# PCB_sch_iter1.net
KiCad netlist of a schematic drawn in EAGLE
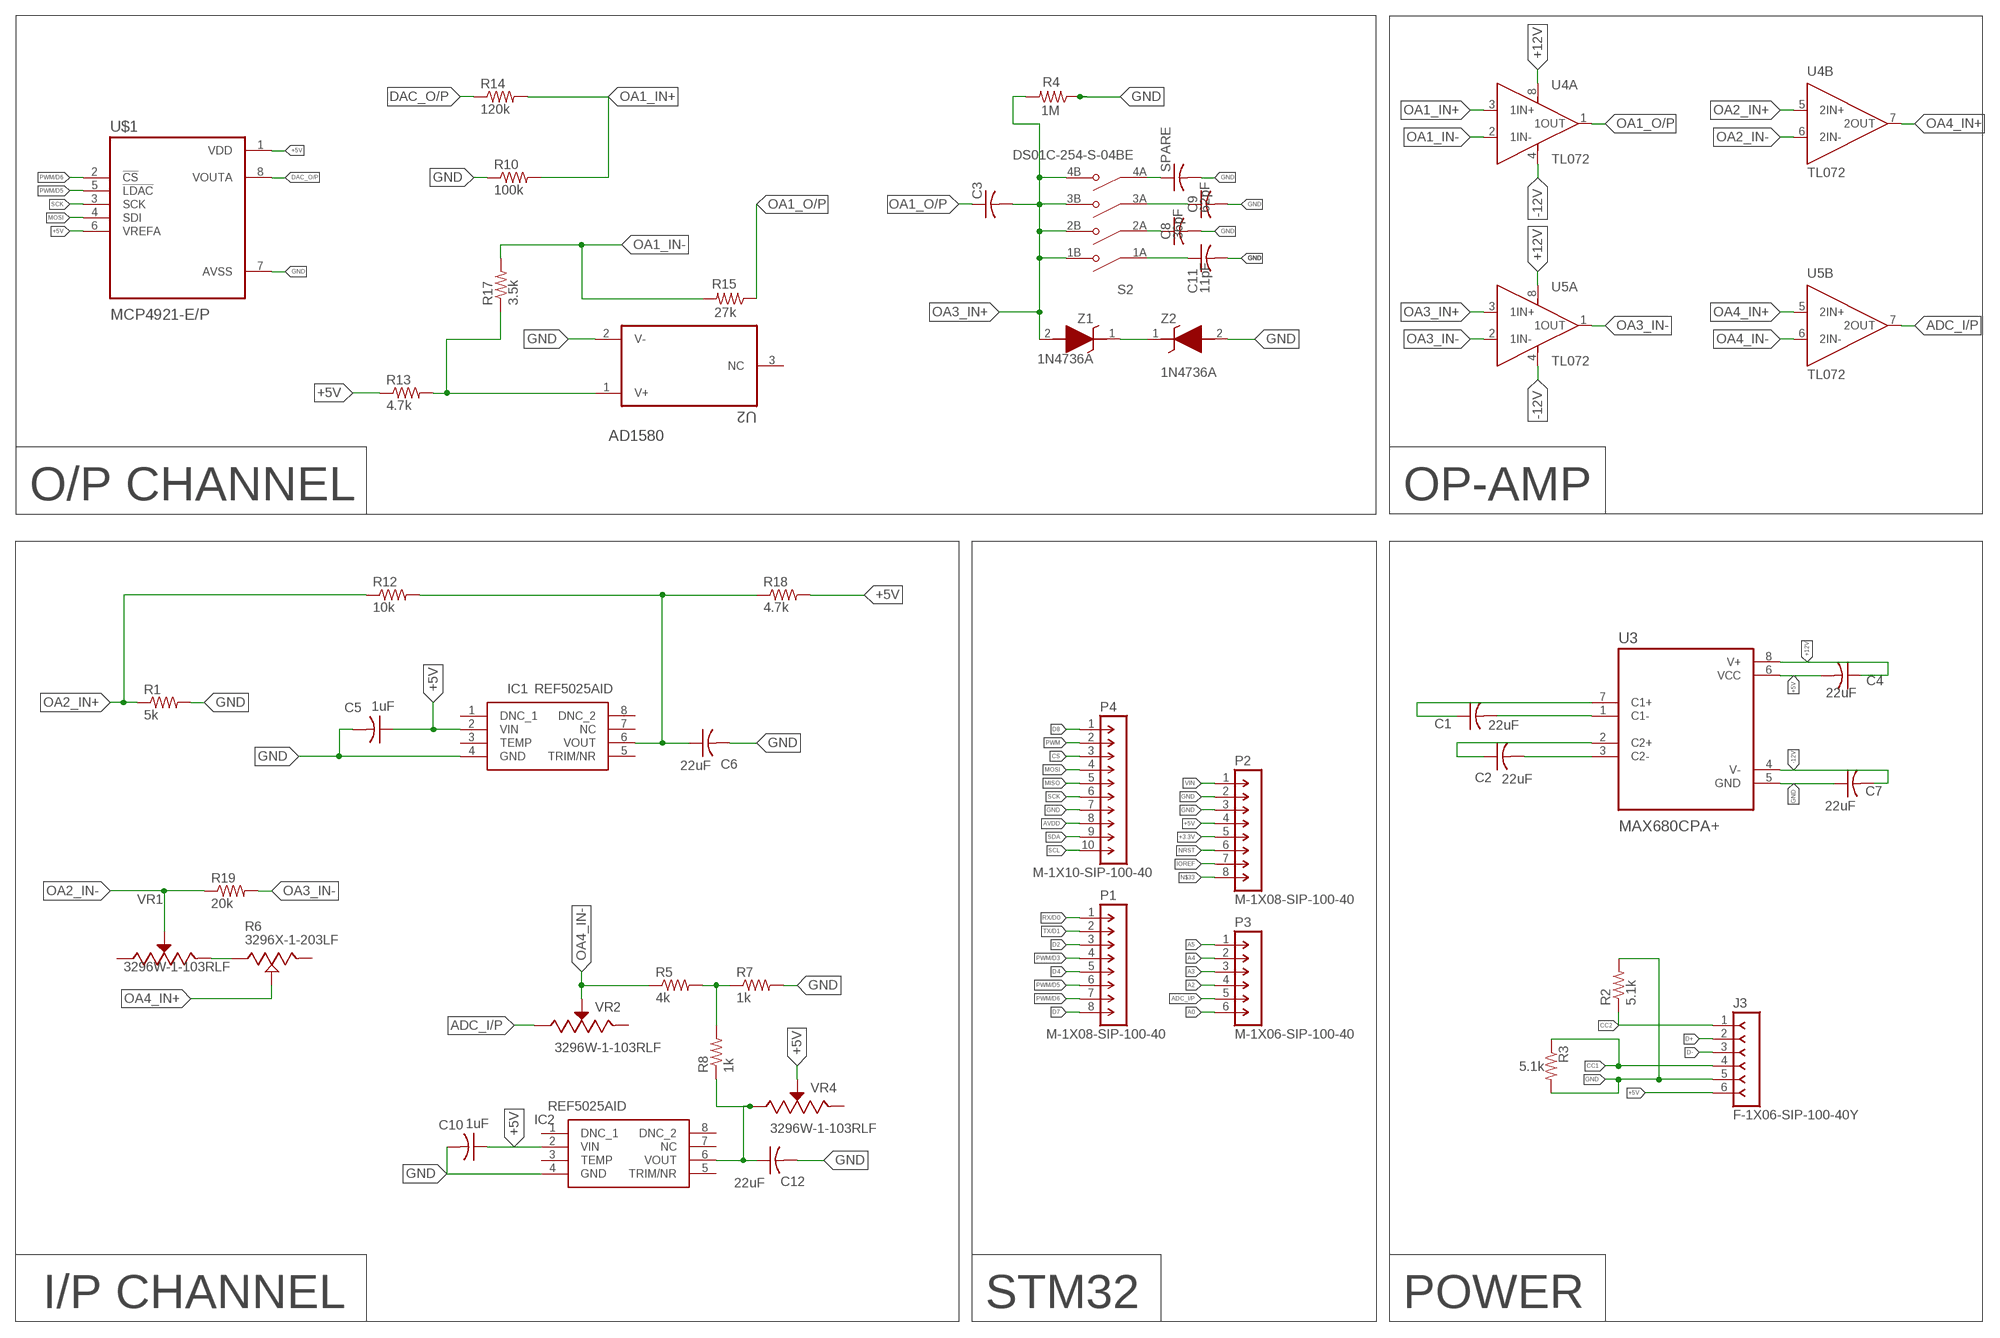
[diagram p0: schematic, sheet 1]

(export (version "E")
  (design (tool "Eeschema 10.0.6"))
  (components
    (comp (ref "C1")
      (value "22uF")
      (footprint "eagle-import:C1206")
      (libsource (lib "eagle-import") (part "C-USC1206"))
    )
    (comp (ref "C2")
      (value "22uF")
      (footprint "eagle-import:C1206")
      (libsource (lib "eagle-import") (part "C-USC1206"))
    )
    (comp (ref "C3")
      (value "C-US050-030X075")
      (footprint "eagle-import:C050-030X075")
      (libsource (lib "eagle-import") (part "C-US050-030X075"))
    )
    (comp (ref "C4")
      (value "22uF")
      (footprint "eagle-import:C1206")
      (libsource (lib "eagle-import") (part "C-USC1206"))
    )
    (comp (ref "C5")
      (value "1uF")
      (footprint "eagle-import:C1206")
      (libsource (lib "eagle-import") (part "C-USC1206"))
    )
    (comp (ref "C6")
      (value "22uF")
      (footprint "eagle-import:C1206")
      (libsource (lib "eagle-import") (part "C-USC1206"))
    )
    (comp (ref "C7")
      (value "22uF")
      (footprint "eagle-import:C1206")
      (libsource (lib "eagle-import") (part "C-USC1206"))
    )
    (comp (ref "C8")
      (value "36pF")
      (footprint "eagle-import:C0805")
      (libsource (lib "eagle-import") (part "C-USC0805"))
    )
    (comp (ref "C9")
      (value "62pF")
      (footprint "eagle-import:C0805")
      (libsource (lib "eagle-import") (part "C-USC0805"))
    )
    (comp (ref "C10")
      (value "1uF")
      (footprint "eagle-import:C1206")
      (libsource (lib "eagle-import") (part "C-USC1206"))
    )
    (comp (ref "C11")
      (value "11pF")
      (footprint "eagle-import:C0805")
      (fields (field (name "SPICEPREFIX") "C"))
      (libsource (lib "eagle-import") (part "C-USC0805"))
    )
    (comp (ref "C12")
      (value "22uF")
      (footprint "eagle-import:C1206")
      (libsource (lib "eagle-import") (part "C-USC1206"))
    )
    (comp (ref "IC1")
      (value "REF5025AID")
      (footprint "eagle-import:SOIC127P600X175-8N")
      (fields (field (name "MOUSER_PART_NUMBER") "595-REF5025AID"))
      (libsource (lib "eagle-import") (part "REF5025AID"))
    )
    (comp (ref "IC2")
      (value "REF5025AID")
      (footprint "eagle-import:SOIC127P600X175-8N")
      (fields (field (name "MOUSER_PART_NUMBER") "595-REF5025AID"))
      (libsource (lib "eagle-import") (part "REF5025AID"))
    )
    (comp (ref "J3")
      (value "F-1X06-SIP-100-40Y")
      (footprint "eagle-import:SIP-100-06-40Y")
      (libsource (lib "eagle-import") (part "F-1X06-SIP-100-40Y"))
    )
    (comp (ref "P1")
      (value "M-1X08-SIP-100-40")
      (footprint "eagle-import:SIP-100-08-40")
      (libsource (lib "eagle-import") (part "M-1X08-SIP-100-40"))
    )
    (comp (ref "P2")
      (value "M-1X08-SIP-100-40")
      (footprint "eagle-import:SIP-100-08-40")
      (libsource (lib "eagle-import") (part "M-1X08-SIP-100-40"))
    )
    (comp (ref "P3")
      (value "M-1X06-SIP-100-40")
      (footprint "eagle-import:SIP-100-06-40")
      (libsource (lib "eagle-import") (part "M-1X06-SIP-100-40"))
    )
    (comp (ref "P4")
      (value "M-1X10-SIP-100-40")
      (footprint "eagle-import:SIP-100-10-40")
      (libsource (lib "eagle-import") (part "M-1X10-SIP-100-40"))
    )
    (comp (ref "R1")
      (value "5k")
      (footprint "eagle-import:M0805")
      (libsource (lib "eagle-import") (part "R-US_M0805"))
    )
    (comp (ref "R2")
      (value "5.1k")
      (footprint "eagle-import:R1206")
      (libsource (lib "eagle-import") (part "R-US_R1206"))
    )
    (comp (ref "R3")
      (value "5.1k")
      (footprint "eagle-import:R1206")
      (libsource (lib "eagle-import") (part "R-US_R1206"))
    )
    (comp (ref "R4")
      (value "1M")
      (footprint "eagle-import:M1206")
      (libsource (lib "eagle-import") (part "R-US_M1206"))
    )
    (comp (ref "R5")
      (value "4k")
      (footprint "eagle-import:M0805")
      (libsource (lib "eagle-import") (part "R-US_M0805"))
    )
    (comp (ref "R6")
      (value "3296X-1-203LF")
      (footprint "eagle-import:TRIM_3296X-1-203LF")
      (fields (field (name "MF") "Bourns"))
      (libsource (lib "eagle-import") (part "3296X-1-203LF"))
    )
    (comp (ref "R7")
      (value "1k")
      (footprint "eagle-import:M0805")
      (libsource (lib "eagle-import") (part "R-US_M0805"))
    )
    (comp (ref "R8")
      (value "1k")
      (footprint "eagle-import:M0805")
      (libsource (lib "eagle-import") (part "R-US_M0805"))
    )
    (comp (ref "R10")
      (value "100k")
      (footprint "eagle-import:M1206")
      (libsource (lib "eagle-import") (part "R-US_M1206"))
    )
    (comp (ref "R12")
      (value "10k")
      (footprint "eagle-import:M1206")
      (libsource (lib "eagle-import") (part "R-US_M1206"))
    )
    (comp (ref "R13")
      (value "4.7k")
      (footprint "eagle-import:M1206")
      (libsource (lib "eagle-import") (part "R-US_M1206"))
    )
    (comp (ref "R14")
      (value "120k")
      (footprint "eagle-import:M1206")
      (libsource (lib "eagle-import") (part "R-US_M1206"))
    )
    (comp (ref "R15")
      (value "27k")
      (footprint "eagle-import:M1206")
      (libsource (lib "eagle-import") (part "R-US_M1206"))
    )
    (comp (ref "R17")
      (value "3.5k")
      (footprint "eagle-import:M1206")
      (libsource (lib "eagle-import") (part "R-US_M1206"))
    )
    (comp (ref "R18")
      (value "4.7k")
      (footprint "eagle-import:M1206")
      (libsource (lib "eagle-import") (part "R-US_M1206"))
    )
    (comp (ref "R19")
      (value "20k")
      (footprint "eagle-import:M0805")
      (libsource (lib "eagle-import") (part "R-US_M0805"))
    )
    (comp (ref "S2")
      (value "DS01C-254-S-04BE")
      (footprint "eagle-import:SW_DS01C-254-S-04BE")
      (fields (field (name "MANUFACTURER") "CUI"))
      (libsource (lib "eagle-import") (part "DS01C-254-S-04BE"))
    )
    (comp (ref "SPARE")
      (value "C-USC0805")
      (footprint "eagle-import:C0805")
      (libsource (lib "eagle-import") (part "C-USC0805"))
    )
    (comp (ref "U$1")
      (value "MCP4921-E/P")
      (footprint "eagle-import:DIP787W46P254L927H533Q8")
      (fields (field (name "MF") "Microchip"))
      (libsource (lib "eagle-import") (part "MCP4921-E/P"))
    )
    (comp (ref "U2")
      (value "AD1580")
      (footprint "eagle-import:SOT96P237X112-3N")
      (libsource (lib "eagle-import") (part "AD1580BRTZ-R2-REEL7"))
    )
    (comp (ref "U3")
      (value "MAX680CPA+")
      (footprint "eagle-import:DIP794W47P254L991H457Q8")
      (fields (field (name "MF") "Maxim Integrated Products"))
      (libsource (lib "eagle-import") (part "MAX680CPA+"))
    )
    (comp (ref "U4")
      (value "TL072")
      (footprint "eagle-import:DIP794W45P254L1060H508Q8")
      (fields (field (name "MF") "Texas Instruments"))
      (libsource (lib "eagle-import") (part "TL072"))
    )
    (comp (ref "U5")
      (value "TL072")
      (footprint "eagle-import:DIP794W45P254L1060H508Q8")
      (fields (field (name "MF") "Texas Instruments"))
      (libsource (lib "eagle-import") (part "TL072"))
    )
    (comp (ref "VR1")
      (value "3296W-1-103RLF")
      (footprint "eagle-import:TRIM_3296W-1-103RLF")
      (fields (field (name "MF") "Bourns"))
      (libsource (lib "eagle-import") (part "3296W-1-103RLF"))
    )
    (comp (ref "VR2")
      (value "3296W-1-103RLF")
      (footprint "eagle-import:TRIM_3296W-1-103RLF")
      (fields (field (name "MF") "Bourns"))
      (libsource (lib "eagle-import") (part "3296W-1-103RLF"))
    )
    (comp (ref "VR4")
      (value "3296W-1-103RLF")
      (footprint "eagle-import:TRIM_3296W-1-103RLF")
      (fields (field (name "MF") "Bourns"))
      (libsource (lib "eagle-import") (part "3296W-1-103RLF"))
    )
    (comp (ref "Z1")
      (value "1N4736A")
      (footprint "eagle-import:DIOAD1413W86L463D238")
      (fields (field (name "MOUSER_PART_NUMBER") "512-1N4736A"))
      (libsource (lib "eagle-import") (part "1N4736A"))
    )
    (comp (ref "Z2")
      (value "1N4736A")
      (footprint "eagle-import:DIOAD1413W86L463D238")
      (fields (field (name "MOUSER_PART_NUMBER") "512-1N4736A"))
      (libsource (lib "eagle-import") (part "1N4736A"))
    )
  )
  (nets
    (net (code "1") (name "+3.3V") (class "Default")
      (node (ref "P2") (pin "5") (pinfunction "5_5") (pintype "passive"))
    )
    (net (code "2") (name "+5V") (class "Default")
      (node (ref "C10") (pin "1") (pinfunction "1_1") (pintype "passive"))
      (node (ref "C4") (pin "2") (pinfunction "2_2") (pintype "passive"))
      (node (ref "C5") (pin "1") (pinfunction "1_1") (pintype "passive"))
      (node (ref "IC1") (pin "2") (pinfunction "VIN_2") (pintype "bidirectional"))
      (node (ref "IC2") (pin "2") (pinfunction "VIN_2") (pintype "bidirectional"))
      (node (ref "J3") (pin "6") (pinfunction "6_6") (pintype "passive"))
      (node (ref "P2") (pin "4") (pinfunction "4_4") (pintype "passive"))
      (node (ref "R13") (pin "1") (pinfunction "1_1") (pintype "passive"))
      (node (ref "R18") (pin "2") (pinfunction "2_2") (pintype "passive"))
      (node (ref "U$1") (pin "1") (pinfunction "VDD_1") (pintype "power_in"))
      (node (ref "U$1") (pin "6") (pinfunction "VREFA_6") (pintype "input"))
      (node (ref "U3") (pin "6") (pinfunction "VCC_6") (pintype "power_in"))
      (node (ref "VR4") (pin "2") (pinfunction "WIPER_2") (pintype "passive"))
    )
    (net (code "3") (name "+12V") (class "Default")
      (node (ref "C4") (pin "1") (pinfunction "1_1") (pintype "passive"))
      (node (ref "U3") (pin "8") (pinfunction "V+_8") (pintype "power_in"))
      (node (ref "U4") (pin "8") (pinfunction "VCC+_8") (pintype "power_in"))
      (node (ref "U5") (pin "8") (pinfunction "VCC+_8") (pintype "power_in"))
    )
    (net (code "4") (name "-12V") (class "Default")
      (node (ref "C7") (pin "2") (pinfunction "2_2") (pintype "passive"))
      (node (ref "U3") (pin "4") (pinfunction "V-_4") (pintype "power_in"))
      (node (ref "U4") (pin "4") (pinfunction "VCC-_4") (pintype "power_in"))
      (node (ref "U5") (pin "4") (pinfunction "VCC-_4") (pintype "power_in"))
    )
    (net (code "5") (name "A0") (class "Default")
      (node (ref "P3") (pin "6") (pinfunction "6_6") (pintype "passive"))
    )
    (net (code "6") (name "A2") (class "Default")
      (node (ref "P3") (pin "4") (pinfunction "4_4") (pintype "passive"))
    )
    (net (code "7") (name "A3") (class "Default")
      (node (ref "P3") (pin "3") (pinfunction "3_3") (pintype "passive"))
    )
    (net (code "8") (name "A4") (class "Default")
      (node (ref "P3") (pin "2") (pinfunction "2_2") (pintype "passive"))
    )
    (net (code "9") (name "A5") (class "Default")
      (node (ref "P3") (pin "1") (pinfunction "1_1") (pintype "passive"))
    )
    (net (code "10") (name "ADC_I{slash}P") (class "Default")
      (node (ref "P3") (pin "5") (pinfunction "5_5") (pintype "passive"))
      (node (ref "U5") (pin "7") (pinfunction "2OUT_7") (pintype "output"))
      (node (ref "VR2") (pin "1") (pinfunction "CCW_1") (pintype "passive"))
    )
    (net (code "11") (name "AVDD") (class "Default")
      (node (ref "P4") (pin "8") (pinfunction "8_8") (pintype "passive"))
    )
    (net (code "12") (name "CC1") (class "Default")
      (node (ref "J3") (pin "4") (pinfunction "4_4") (pintype "passive"))
      (node (ref "R3") (pin "1") (pinfunction "1_1") (pintype "passive"))
    )
    (net (code "13") (name "CC2") (class "Default")
      (node (ref "J3") (pin "1") (pinfunction "1_1") (pintype "passive"))
      (node (ref "R2") (pin "1") (pinfunction "1_1") (pintype "passive"))
    )
    (net (code "14") (name "CS") (class "Default")
      (node (ref "P4") (pin "3") (pinfunction "3_3") (pintype "passive"))
    )
    (net (code "15") (name "D+") (class "Default")
      (node (ref "J3") (pin "2") (pinfunction "2_2") (pintype "passive"))
    )
    (net (code "16") (name "D-") (class "Default")
      (node (ref "J3") (pin "3") (pinfunction "3_3") (pintype "passive"))
    )
    (net (code "17") (name "D2") (class "Default")
      (node (ref "P1") (pin "3") (pinfunction "3_3") (pintype "passive"))
    )
    (net (code "18") (name "D4") (class "Default")
      (node (ref "P1") (pin "5") (pinfunction "5_5") (pintype "passive"))
    )
    (net (code "19") (name "D7") (class "Default")
      (node (ref "P1") (pin "8") (pinfunction "8_8") (pintype "passive"))
    )
    (net (code "20") (name "D8") (class "Default")
      (node (ref "P4") (pin "1") (pinfunction "1_1") (pintype "passive"))
    )
    (net (code "21") (name "DAC_O{slash}P") (class "Default")
      (node (ref "R14") (pin "1") (pinfunction "1_1") (pintype "passive"))
      (node (ref "U$1") (pin "8") (pinfunction "VOUTA_8") (pintype "output"))
    )
    (net (code "22") (name "GND") (class "Default")
      (node (ref "C10") (pin "2") (pinfunction "2_2") (pintype "passive"))
      (node (ref "C11") (pin "2") (pinfunction "2_2") (pintype "passive"))
      (node (ref "C12") (pin "2") (pinfunction "2_2") (pintype "passive"))
      (node (ref "C5") (pin "2") (pinfunction "2_2") (pintype "passive"))
      (node (ref "C6") (pin "2") (pinfunction "2_2") (pintype "passive"))
      (node (ref "C7") (pin "1") (pinfunction "1_1") (pintype "passive"))
      (node (ref "C8") (pin "2") (pinfunction "2_2") (pintype "passive"))
      (node (ref "C9") (pin "2") (pinfunction "2_2") (pintype "passive"))
      (node (ref "IC1") (pin "4") (pinfunction "GND_4") (pintype "bidirectional"))
      (node (ref "IC2") (pin "4") (pinfunction "GND_4") (pintype "bidirectional"))
      (node (ref "J3") (pin "5") (pinfunction "5_5") (pintype "passive"))
      (node (ref "P2") (pin "2") (pinfunction "2_2") (pintype "passive"))
      (node (ref "P2") (pin "3") (pinfunction "3_3") (pintype "passive"))
      (node (ref "P4") (pin "7") (pinfunction "7_7") (pintype "passive"))
      (node (ref "R1") (pin "2") (pinfunction "2_2") (pintype "passive"))
      (node (ref "R10") (pin "1") (pinfunction "1_1") (pintype "passive"))
      (node (ref "R2") (pin "2") (pinfunction "2_2") (pintype "passive"))
      (node (ref "R3") (pin "2") (pinfunction "2_2") (pintype "passive"))
      (node (ref "R4") (pin "1") (pinfunction "1_1") (pintype "passive"))
      (node (ref "R7") (pin "2") (pinfunction "2_2") (pintype "passive"))
      (node (ref "SPARE") (pin "2") (pinfunction "2_2") (pintype "passive"))
      (node (ref "U$1") (pin "7") (pinfunction "AVSS_7") (pintype "power_in"))
      (node (ref "U2") (pin "2") (pinfunction "V-_2") (pintype "power_in"))
      (node (ref "U3") (pin "5") (pinfunction "GND_5") (pintype "power_in"))
      (node (ref "Z2") (pin "2") (pinfunction "A_2") (pintype "bidirectional"))
    )
    (net (code "23") (name "IOREF") (class "Default")
      (node (ref "P2") (pin "7") (pinfunction "7_7") (pintype "passive"))
    )
    (net (code "24") (name "MISO") (class "Default")
      (node (ref "P4") (pin "5") (pinfunction "5_5") (pintype "passive"))
    )
    (net (code "25") (name "MOSI") (class "Default")
      (node (ref "P4") (pin "4") (pinfunction "4_4") (pintype "passive"))
      (node (ref "U$1") (pin "4") (pinfunction "SDI_4") (pintype "input"))
    )
    (net (code "26") (name "N$33") (class "Default")
      (node (ref "P2") (pin "8") (pinfunction "8_8") (pintype "passive"))
    )
    (net (code "27") (name "NRST") (class "Default")
      (node (ref "P2") (pin "6") (pinfunction "6_6") (pintype "passive"))
    )
    (net (code "28") (name "Net-(IC1-VOUT)") (class "Default")
      (node (ref "C6") (pin "1") (pinfunction "1_1") (pintype "passive"))
      (node (ref "IC1") (pin "6") (pinfunction "VOUT_6") (pintype "bidirectional"))
      (node (ref "R12") (pin "2") (pinfunction "2_2") (pintype "passive"))
      (node (ref "R18") (pin "1") (pinfunction "1_1") (pintype "passive"))
    )
    (net (code "29") (name "Net-(IC2-VOUT)") (class "Default")
      (node (ref "C12") (pin "1") (pinfunction "1_1") (pintype "passive"))
      (node (ref "IC2") (pin "6") (pinfunction "VOUT_6") (pintype "bidirectional"))
      (node (ref "R8") (pin "1") (pinfunction "1_1") (pintype "passive"))
      (node (ref "VR4") (pin "1") (pinfunction "CCW_1") (pintype "passive"))
    )
    (net (code "30") (name "Net-(R5-Pad2)") (class "Default")
      (node (ref "R5") (pin "2") (pinfunction "2_2") (pintype "passive"))
      (node (ref "R7") (pin "1") (pinfunction "1_1") (pintype "passive"))
      (node (ref "R8") (pin "2") (pinfunction "2_2") (pintype "passive"))
    )
    (net (code "31") (name "Net-(R6-CCW)") (class "Default")
      (node (ref "R6") (pin "1") (pinfunction "CCW_1") (pintype "passive"))
      (node (ref "VR1") (pin "3") (pinfunction "CW_3") (pintype "passive"))
    )
    (net (code "32") (name "Net-(S2-COM1)") (class "Default")
      (node (ref "C11") (pin "1") (pinfunction "1_1") (pintype "passive"))
      (node (ref "S2") (pin "1A") (pinfunction "COM1_1A") (pintype "passive"))
    )
    (net (code "33") (name "Net-(S2-COM2)") (class "Default")
      (node (ref "C8") (pin "1") (pinfunction "1_1") (pintype "passive"))
      (node (ref "S2") (pin "2A") (pinfunction "COM2_2A") (pintype "passive"))
    )
    (net (code "34") (name "Net-(S2-COM3)") (class "Default")
      (node (ref "C9") (pin "1") (pinfunction "1_1") (pintype "passive"))
      (node (ref "S2") (pin "3A") (pinfunction "COM3_3A") (pintype "passive"))
    )
    (net (code "35") (name "Net-(S2-COM4)") (class "Default")
      (node (ref "S2") (pin "4A") (pinfunction "COM4_4A") (pintype "passive"))
      (node (ref "SPARE") (pin "1") (pinfunction "1_1") (pintype "passive"))
    )
    (net (code "36") (name "Net-(U2-V+)") (class "Default")
      (node (ref "R13") (pin "2") (pinfunction "2_2") (pintype "passive"))
      (node (ref "R17") (pin "1") (pinfunction "1_1") (pintype "passive"))
      (node (ref "U2") (pin "1") (pinfunction "V+_1") (pintype "power_in"))
    )
    (net (code "37") (name "Net-(U3-C1+)") (class "Default")
      (node (ref "C1") (pin "1") (pinfunction "1_1") (pintype "passive"))
      (node (ref "U3") (pin "7") (pinfunction "C1+_7") (pintype "passive"))
    )
    (net (code "38") (name "Net-(U3-C1-)") (class "Default")
      (node (ref "C1") (pin "2") (pinfunction "2_2") (pintype "passive"))
      (node (ref "U3") (pin "1") (pinfunction "C1-_1") (pintype "passive"))
    )
    (net (code "39") (name "Net-(U3-C2+)") (class "Default")
      (node (ref "C2") (pin "1") (pinfunction "1_1") (pintype "passive"))
      (node (ref "U3") (pin "2") (pinfunction "C2+_2") (pintype "passive"))
    )
    (net (code "40") (name "Net-(U3-C2-)") (class "Default")
      (node (ref "C2") (pin "2") (pinfunction "2_2") (pintype "passive"))
      (node (ref "U3") (pin "3") (pinfunction "C2-_3") (pintype "passive"))
    )
    (net (code "41") (name "Net-(Z1-K)") (class "Default")
      (node (ref "Z1") (pin "1") (pinfunction "K_1") (pintype "bidirectional"))
      (node (ref "Z2") (pin "1") (pinfunction "K_1") (pintype "bidirectional"))
    )
    (net (code "42") (name "OA1_IN+") (class "Default")
      (node (ref "R10") (pin "2") (pinfunction "2_2") (pintype "passive"))
      (node (ref "R14") (pin "2") (pinfunction "2_2") (pintype "passive"))
      (node (ref "U4") (pin "3") (pinfunction "1IN+_3") (pintype "input"))
    )
    (net (code "43") (name "OA1_IN-") (class "Default")
      (node (ref "R15") (pin "2") (pinfunction "2_2") (pintype "passive"))
      (node (ref "R17") (pin "2") (pinfunction "2_2") (pintype "passive"))
      (node (ref "U4") (pin "2") (pinfunction "1IN-_2") (pintype "input"))
    )
    (net (code "44") (name "OA1_O{slash}P") (class "Default")
      (node (ref "C3") (pin "1") (pinfunction "1_1") (pintype "passive"))
      (node (ref "R15") (pin "1") (pinfunction "1_1") (pintype "passive"))
      (node (ref "U4") (pin "1") (pinfunction "1OUT_1") (pintype "output"))
    )
    (net (code "45") (name "OA2_IN+") (class "Default")
      (node (ref "R1") (pin "1") (pinfunction "1_1") (pintype "passive"))
      (node (ref "R12") (pin "1") (pinfunction "1_1") (pintype "passive"))
      (node (ref "U4") (pin "5") (pinfunction "2IN+_5") (pintype "input"))
    )
    (net (code "46") (name "OA2_IN-") (class "Default")
      (node (ref "R19") (pin "1") (pinfunction "1_1") (pintype "passive"))
      (node (ref "U4") (pin "6") (pinfunction "2IN-_6") (pintype "input"))
      (node (ref "VR1") (pin "2") (pinfunction "WIPER_2") (pintype "passive"))
    )
    (net (code "47") (name "OA3_IN+") (class "Default")
      (node (ref "C3") (pin "2") (pinfunction "2_2") (pintype "passive"))
      (node (ref "R4") (pin "2") (pinfunction "2_2") (pintype "passive"))
      (node (ref "S2") (pin "1B") (pinfunction "NO1_1B") (pintype "passive"))
      (node (ref "S2") (pin "2B") (pinfunction "NO2_2B") (pintype "passive"))
      (node (ref "S2") (pin "3B") (pinfunction "NO3_3B") (pintype "passive"))
      (node (ref "S2") (pin "4B") (pinfunction "NO4_4B") (pintype "passive"))
      (node (ref "U5") (pin "3") (pinfunction "1IN+_3") (pintype "input"))
      (node (ref "Z1") (pin "2") (pinfunction "A_2") (pintype "bidirectional"))
    )
    (net (code "48") (name "OA3_IN-") (class "Default")
      (node (ref "R19") (pin "2") (pinfunction "2_2") (pintype "passive"))
      (node (ref "U5") (pin "1") (pinfunction "1OUT_1") (pintype "output"))
      (node (ref "U5") (pin "2") (pinfunction "1IN-_2") (pintype "input"))
    )
    (net (code "49") (name "OA4_IN+") (class "Default")
      (node (ref "R6") (pin "2") (pinfunction "WIPER_2") (pintype "passive"))
      (node (ref "U4") (pin "7") (pinfunction "2OUT_7") (pintype "output"))
      (node (ref "U5") (pin "5") (pinfunction "2IN+_5") (pintype "input"))
    )
    (net (code "50") (name "OA4_IN-") (class "Default")
      (node (ref "R5") (pin "1") (pinfunction "1_1") (pintype "passive"))
      (node (ref "U5") (pin "6") (pinfunction "2IN-_6") (pintype "input"))
      (node (ref "VR2") (pin "2") (pinfunction "WIPER_2") (pintype "passive"))
    )
    (net (code "51") (name "PWM") (class "Default")
      (node (ref "P4") (pin "2") (pinfunction "2_2") (pintype "passive"))
    )
    (net (code "52") (name "PWM{slash}D3") (class "Default")
      (node (ref "P1") (pin "4") (pinfunction "4_4") (pintype "passive"))
    )
    (net (code "53") (name "PWM{slash}D5") (class "Default")
      (node (ref "P1") (pin "6") (pinfunction "6_6") (pintype "passive"))
      (node (ref "U$1") (pin "5") (pinfunction "~{LDAC}_5") (pintype "input"))
    )
    (net (code "54") (name "PWM{slash}D6") (class "Default")
      (node (ref "P1") (pin "7") (pinfunction "7_7") (pintype "passive"))
      (node (ref "U$1") (pin "2") (pinfunction "~{CS}_2") (pintype "input"))
    )
    (net (code "55") (name "RX{slash}D0") (class "Default")
      (node (ref "P1") (pin "1") (pinfunction "1_1") (pintype "passive"))
    )
    (net (code "56") (name "SCK") (class "Default")
      (node (ref "P4") (pin "6") (pinfunction "6_6") (pintype "passive"))
      (node (ref "U$1") (pin "3") (pinfunction "SCK_3") (pintype "input"))
    )
    (net (code "57") (name "SCL") (class "Default")
      (node (ref "P4") (pin "10") (pinfunction "10_10") (pintype "passive"))
    )
    (net (code "58") (name "SDA") (class "Default")
      (node (ref "P4") (pin "9") (pinfunction "9_9") (pintype "passive"))
    )
    (net (code "59") (name "TX{slash}D1") (class "Default")
      (node (ref "P1") (pin "2") (pinfunction "2_2") (pintype "passive"))
    )
    (net (code "60") (name "VIN") (class "Default")
      (node (ref "P2") (pin "1") (pinfunction "1_1") (pintype "passive"))
    )
    (net (code "61") (name "unconnected-(IC1-DNC_1-Pad1)") (class "Default")
      (node (ref "IC1") (pin "1") (pinfunction "DNC_1_1") (pintype "bidirectional"))
    )
    (net (code "62") (name "unconnected-(IC1-DNC_2-Pad8)") (class "Default")
      (node (ref "IC1") (pin "8") (pinfunction "DNC_2_8") (pintype "bidirectional"))
    )
    (net (code "63") (name "unconnected-(IC1-NC-Pad7)") (class "Default")
      (node (ref "IC1") (pin "7") (pinfunction "NC_7") (pintype "no_connect"))
    )
    (net (code "64") (name "unconnected-(IC1-TEMP-Pad3)") (class "Default")
      (node (ref "IC1") (pin "3") (pinfunction "TEMP_3") (pintype "bidirectional"))
    )
    (net (code "65") (name "unconnected-(IC1-TRIM{slash}NR-Pad5)") (class "Default")
      (node (ref "IC1") (pin "5") (pinfunction "TRIM/NR_5") (pintype "bidirectional"))
    )
    (net (code "66") (name "unconnected-(IC2-DNC_1-Pad1)") (class "Default")
      (node (ref "IC2") (pin "1") (pinfunction "DNC_1_1") (pintype "bidirectional"))
    )
    (net (code "67") (name "unconnected-(IC2-DNC_2-Pad8)") (class "Default")
      (node (ref "IC2") (pin "8") (pinfunction "DNC_2_8") (pintype "bidirectional"))
    )
    (net (code "68") (name "unconnected-(IC2-NC-Pad7)") (class "Default")
      (node (ref "IC2") (pin "7") (pinfunction "NC_7") (pintype "no_connect"))
    )
    (net (code "69") (name "unconnected-(IC2-TEMP-Pad3)") (class "Default")
      (node (ref "IC2") (pin "3") (pinfunction "TEMP_3") (pintype "bidirectional"))
    )
    (net (code "70") (name "unconnected-(IC2-TRIM{slash}NR-Pad5)") (class "Default")
      (node (ref "IC2") (pin "5") (pinfunction "TRIM/NR_5") (pintype "bidirectional"))
    )
    (net (code "71") (name "unconnected-(R6-CW-Pad3)") (class "Default")
      (node (ref "R6") (pin "3") (pinfunction "CW_3") (pintype "passive"))
    )
    (net (code "72") (name "unconnected-(U2-NC-Pad3)") (class "Default")
      (node (ref "U2") (pin "3") (pinfunction "NC_3") (pintype "bidirectional"))
    )
    (net (code "73") (name "unconnected-(VR1-CCW-Pad1)") (class "Default")
      (node (ref "VR1") (pin "1") (pinfunction "CCW_1") (pintype "passive"))
    )
    (net (code "74") (name "unconnected-(VR2-CW-Pad3)") (class "Default")
      (node (ref "VR2") (pin "3") (pinfunction "CW_3") (pintype "passive"))
    )
    (net (code "75") (name "unconnected-(VR4-CW-Pad3)") (class "Default")
      (node (ref "VR4") (pin "3") (pinfunction "CW_3") (pintype "passive"))
    )
  )
)
